# Current_Me.net
KiCad netlist of a schematic drawn in Altium Designer
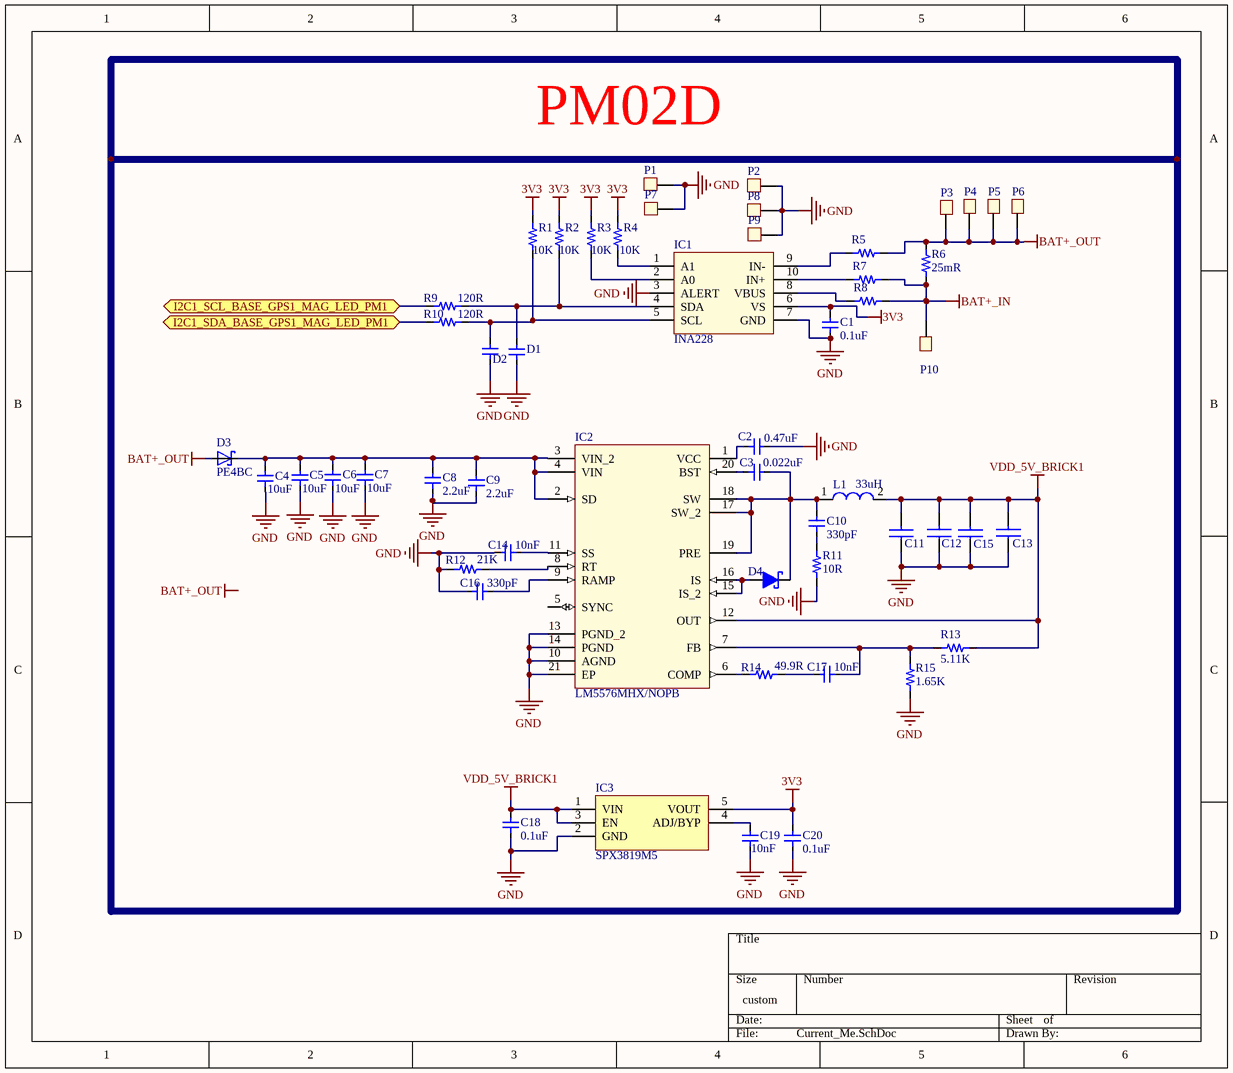
[diagram p0: Current_Me.SchDoc]

(export (version "E")
  (design (tool "Eeschema 10.0.6"))
  (components
    (comp (ref "C1")
      (value "0.1uF")
      (footprint "C0603")
      (description "CAP CER 0.1UF 25V X7R 0603")
      (libsource (lib "UAV_mainboard") (part "CC0603KRX7R8BB104"))
    )
    (comp (ref "C2")
      (value "0.47uF")
      (footprint "C0603")
      (description "0.47 µF ±10% 50V Ceramic Capacitor X5R 0603 (1608 Metric)")
      (libsource (lib "UAV_mainboard") (part "CC0603KRX5R9BB474"))
    )
    (comp (ref "C3")
      (value "0.022uF")
      (footprint "C0603")
      (description "0.022 µF ±10% 50V Ceramic Capacitor X7R 0603 (1608 Metric)")
      (libsource (lib "UAV_mainboard") (part "0603B223K500CT"))
    )
    (comp (ref "C4")
      (value "10uF")
      (footprint "C1206")
      (description "10 µF ±10% 100V Ceramic Capacitor X6S 1206 (3216 Metric)")
      (libsource (lib "UAV_mainboard") (part "C3216X6S2A106K160AC"))
    )
    (comp (ref "C5")
      (value "10uF")
      (footprint "C1206")
      (description "10 µF ±10% 100V Ceramic Capacitor X6S 1206 (3216 Metric)")
      (libsource (lib "UAV_mainboard") (part "C3216X6S2A106K160AC"))
    )
    (comp (ref "C6")
      (value "10uF")
      (footprint "C1206")
      (description "10 µF ±10% 100V Ceramic Capacitor X6S 1206 (3216 Metric)")
      (libsource (lib "UAV_mainboard") (part "C3216X6S2A106K160AC"))
    )
    (comp (ref "C7")
      (value "10uF")
      (footprint "C1206")
      (description "10 µF ±10% 100V Ceramic Capacitor X6S 1206 (3216 Metric)")
      (libsource (lib "UAV_mainboard") (part "C3216X6S2A106K160AC"))
    )
    (comp (ref "C8")
      (value "2.2uF")
      (footprint "C0603")
      (description "2.2 µF ±10% 10V Ceramic Capacitor X5R 0603 (1608 Metric)")
      (libsource (lib "UAV_mainboard") (part "CC0603KPX5R6BB225"))
    )
    (comp (ref "C9")
      (value "2.2uF")
      (footprint "C0603")
      (description "2.2 µF ±10% 10V Ceramic Capacitor X5R 0603 (1608 Metric)")
      (libsource (lib "UAV_mainboard") (part "CC0603KPX5R6BB225"))
    )
    (comp (ref "C10")
      (value "330pF")
      (footprint "C0603")
      (description "330 pF ±10% 25V Ceramic Capacitor X7R 0603 (1608 Metric)")
      (libsource (lib "UAV_mainboard") (part "CC0603KRX7R8BB331"))
    )
    (comp (ref "C11")
      (value "C2012X5R1A226M125AB")
      (footprint "C0805")
      (description "Multilayer Ceramic Capacitors MLCC - SMD/SMT 0805 10V 22uF X5R 20% T: 1.25mm")
      (libsource (lib "GPS_V3") (part "C2012X5R1A226M125AB"))
    )
    (comp (ref "C12")
      (value "C2012X5R1A226M125AB")
      (footprint "C0805")
      (description "Multilayer Ceramic Capacitors MLCC - SMD/SMT 0805 10V 22uF X5R 20% T: 1.25mm")
      (libsource (lib "GPS_V3") (part "C2012X5R1A226M125AB"))
    )
    (comp (ref "C13")
      (value "C2012X5R1A226M125AB")
      (footprint "C0805")
      (description "Multilayer Ceramic Capacitors MLCC - SMD/SMT 0805 10V 22uF X5R 20% T: 1.25mm")
      (libsource (lib "GPS_V3") (part "C2012X5R1A226M125AB"))
    )
    (comp (ref "C14")
      (value "10nF")
      (footprint "C0603")
      (description "10000 pF ±5% 25V Ceramic Capacitor X7R 0603 (1608 Metric)")
      (libsource (lib "UAV_mainboard") (part "CC0603JRX7R8BB103"))
    )
    (comp (ref "C15")
      (value "C2012X5R1A226M125AB")
      (footprint "C0805")
      (description "Multilayer Ceramic Capacitors MLCC - SMD/SMT 0805 10V 22uF X5R 20% T: 1.25mm")
      (libsource (lib "GPS_V3") (part "C2012X5R1A226M125AB"))
    )
    (comp (ref "C16")
      (value "330pF")
      (footprint "C0603")
      (description "330 pF ±10% 25V Ceramic Capacitor X7R 0603 (1608 Metric)")
      (libsource (lib "UAV_mainboard") (part "CC0603KRX7R8BB331"))
    )
    (comp (ref "C17")
      (value "10nF")
      (footprint "C0603")
      (description "10000 pF ±5% 25V Ceramic Capacitor X7R 0603 (1608 Metric)")
      (libsource (lib "UAV_mainboard") (part "CC0603JRX7R8BB103"))
    )
    (comp (ref "C18")
      (value "0.1uF")
      (footprint "C0603")
      (description "CAP CER 0.1UF 25V X7R 0603")
      (libsource (lib "UAV_mainboard") (part "CC0603KRX7R8BB104"))
    )
    (comp (ref "C19")
      (value "10nF")
      (footprint "C0603")
      (description "10000 pF ±5% 25V Ceramic Capacitor X7R 0603 (1608 Metric)")
      (libsource (lib "UAV_mainboard") (part "CC0603JRX7R8BB103"))
    )
    (comp (ref "C20")
      (value "0.1uF")
      (footprint "C0603")
      (description "CAP CER 0.1UF 25V X7R 0603")
      (libsource (lib "UAV_mainboard") (part "CC0603KRX7R8BB104"))
    )
    (comp (ref "D1")
      (value "PESD0402-140")
      (footprint "PESD0402-140")
      (description "40V Clamp - Ipp Tvs Diode Surface Mount 0402")
      (libsource (lib "UAV_mainboard") (part "PESD0402-140"))
    )
    (comp (ref "D2")
      (value "PESD0402-140")
      (footprint "PESD0402-140")
      (description "40V Clamp - Ipp Tvs Diode Surface Mount 0402")
      (libsource (lib "UAV_mainboard") (part "PESD0402-140"))
    )
    (comp (ref "D3")
      (value "PE4BC")
      (footprint "PE4BC")
      (description "Diode 100 V 4A Surface Mount DO-214AB (SMC)")
      (libsource (lib "UAV_mainboard") (part "PE4BC"))
    )
    (comp (ref "D4")
      (value "MBRS3100T3G")
      (footprint "MBRS3100T3G")
      (description "DIODE SCHOTTKY 100V 3A SMC")
      (libsource (lib "UAV_mainboard") (part "MBRS3100T3G"))
    )
    (comp (ref "IC1")
      (value "INA228")
      (footprint "VSSOP10")
      (description "Current & Power Monitors & Regulators AEC-Q100 85-V 20-b it ultraprecise I")
      (libsource (lib "UAV_mainboard") (part "INA228AQDGSRQ1"))
    )
    (comp (ref "IC2")
      (value "LM5576MHX/NOPB")
      (footprint "20HTSSOP")
      (description "IC REG BUCK ADJ 3A 20HTSSOP")
      (libsource (lib "UAV_mainboard") (part "LM5576MHX/NOPB"))
    )
    (comp (ref "IC3")
      (value "SPX3819M5")
      (footprint "SOT23-5")
      (description "IC REG LINEAR 3V 500MA SOT23-5")
      (libsource (lib "UAV_mainboard") (part "SPX3819M5-L-3-0/TR"))
    )
    (comp (ref "L1")
      (value "33uH")
      (footprint "MGAH1005330M-10")
      (description "Power Inductors - SMD 33uH 0.075ohm 5A")
      (libsource (lib "UAV_mainboard") (part "MGAH1005330M-10"))
    )
    (comp (ref "P1") (value "PAD_hàn 5x5") (footprint "PAD 5x5") (libsource (lib "") (part "PAD_hàn 5x5_2")))
    (comp (ref "P2") (value "PAD_hàn 5x5") (footprint "PAD 5x5") (libsource (lib "") (part "PAD_hàn 5x5_2")))
    (comp (ref "P3")
      (value "PAD_hàn 5x5")
      (footprint "PAD 5x5")
      (libsource (lib "UAV_mainboard") (part "PAD_hàn 5x5"))
    )
    (comp (ref "P4")
      (value "PAD_hàn 5x5")
      (footprint "PAD 5x5")
      (libsource (lib "UAV_mainboard") (part "PAD_hàn 5x5"))
    )
    (comp (ref "P5")
      (value "PAD_hàn 5x5")
      (footprint "PAD 5x5")
      (libsource (lib "UAV_mainboard") (part "PAD_hàn 5x5"))
    )
    (comp (ref "P6")
      (value "PAD_hàn 5x5")
      (footprint "PAD 5x5")
      (libsource (lib "UAV_mainboard") (part "PAD_hàn 5x5"))
    )
    (comp (ref "P7") (value "PAD_hàn 5x5") (footprint "PAD 5x5") (libsource (lib "") (part "PAD_hàn 5x5_2")))
    (comp (ref "P8") (value "PAD_hàn 5x5") (footprint "PAD 5x5") (libsource (lib "") (part "PAD_hàn 5x5_2")))
    (comp (ref "P9") (value "PAD_hàn 5x5") (footprint "PAD 5x5") (libsource (lib "") (part "PAD_hàn 5x5_2")))
    (comp (ref "P10") (value "PAD_hàn 5x5") (footprint "PAD 5x5") (libsource (lib "") (part "PAD_hàn 5x5_1")))
    (comp (ref "R1")
      (value "10K")
      (footprint "R0402")
      (description "RES SMD 10K OHM 1% 1/16W 0402")
      (libsource (lib "UAV_mainboard") (part "RC1005F103CS"))
    )
    (comp (ref "R2")
      (value "10K")
      (footprint "R0402")
      (description "RES SMD 10K OHM 1% 1/16W 0402")
      (libsource (lib "UAV_mainboard") (part "RC1005F103CS"))
    )
    (comp (ref "R3")
      (value "10K")
      (footprint "R0402")
      (description "RES SMD 10K OHM 1% 1/16W 0402")
      (libsource (lib "UAV_mainboard") (part "RC1005F103CS"))
    )
    (comp (ref "R4")
      (value "10K")
      (footprint "R0402")
      (description "RES SMD 10K OHM 1% 1/16W 0402")
      (libsource (lib "UAV_mainboard") (part "RC1005F103CS"))
    )
    (comp (ref "R5")
      (value "0R/0402")
      (footprint "R0402")
      (libsource (lib "UAV_mainboard") (part "CR0402AJ/-000GAS"))
    )
    (comp (ref "R6")
      (value "25mR")
      (footprint "R2818")
      (libsource (lib "UAV_mainboard") (part "WSHP2818R0250FEA"))
    )
    (comp (ref "R7")
      (value "0R/0402")
      (footprint "R0402")
      (libsource (lib "UAV_mainboard") (part "CR0402AJ/-000GAS"))
    )
    (comp (ref "R8")
      (value "0R/0402")
      (footprint "R0402")
      (libsource (lib "UAV_mainboard") (part "CR0402AJ/-000GAS"))
    )
    (comp (ref "R9")
      (value "120R")
      (footprint "R0402")
      (description "120 Ohms ±1% 0.063W, 1/16W Chip Resistor 0402 (1005 Metric) Moisture Resistant Thick Film")
      (libsource (lib "UAV_mainboard") (part "RC0402FR-07120RL"))
    )
    (comp (ref "R10")
      (value "120R")
      (footprint "R0402")
      (description "120 Ohms ±1% 0.063W, 1/16W Chip Resistor 0402 (1005 Metric) Moisture Resistant Thick Film")
      (libsource (lib "UAV_mainboard") (part "RC0402FR-07120RL"))
    )
    (comp (ref "R11")
      (value "10R")
      (footprint "R0603")
      (description "10 Ohms ±1% 0.1W, 1/10W Chip Resistor 0603 (1608 Metric) Automotive AEC-Q200 Thick Film")
      (libsource (lib "UAV_mainboard") (part "RMCF0603FT10R0"))
    )
    (comp (ref "R12")
      (value "21K")
      (footprint "R0402")
      (description "21 kOhms ±1% 0.063W, 1/16W Chip Resistor 0402 (1005 Metric) Moisture Resistant Thick Film")
      (libsource (lib "UAV_mainboard") (part "RC0402FR-0721KL"))
    )
    (comp (ref "R13")
      (value "5.11K")
      (footprint "R0402")
      (description "5.11 kOhms ±1% 0.1W, 1/10W Chip Resistor 0402 (1005 Metric) Automotive AEC-Q200 Thick Film")
      (libsource (lib "UAV_mainboard") (part "ERJ-2RKF5111X"))
    )
    (comp (ref "R14")
      (value "49.9R")
      (footprint "R0402")
      (libsource (lib "UAV_mainboard") (part "CRT0402ABY-49R9GLF"))
    )
    (comp (ref "R15")
      (value "1.65K")
      (footprint "R0402")
      (description "RES 1.65K OHM 1% 1/16W 0402")
      (libsource (lib "UAV_mainboard") (part "RC0402FR-071K65L"))
    )
  )
  (nets
    (net (code "1") (name "/I2C1_SCL_BASE_GPS1_MAG_LED_PM1") (class "Default")
      (node (ref "R9") (pin "1") (pinfunction "1_1") (pintype "passive"))
    )
    (net (code "2") (name "/I2C1_SDA_BASE_GPS1_MAG_LED_PM1") (class "Default")
      (node (ref "R10") (pin "1") (pinfunction "1_1") (pintype "passive"))
    )
    (net (code "3") (name "3V3") (class "Default")
      (node (ref "C1") (pin "2") (pinfunction "2_2") (pintype "passive"))
      (node (ref "C20") (pin "2") (pinfunction "2_2") (pintype "passive"))
      (node (ref "IC1") (pin "6") (pinfunction "VS_6") (pintype "passive"))
      (node (ref "IC3") (pin "5") (pinfunction "VOUT_5") (pintype "passive"))
      (node (ref "R1") (pin "2") (pinfunction "2_2") (pintype "passive"))
      (node (ref "R2") (pin "2") (pinfunction "2_2") (pintype "passive"))
      (node (ref "R3") (pin "2") (pinfunction "2_2") (pintype "passive"))
      (node (ref "R4") (pin "2") (pinfunction "2_2") (pintype "passive"))
    )
    (net (code "4") (name "BAT+_IN") (class "Default")
      (node (ref "P10") (pin "1") (pinfunction "1_1") (pintype "passive"))
      (node (ref "R6") (pin "1") (pinfunction "1_1") (pintype "passive"))
      (node (ref "R7") (pin "2") (pinfunction "2_2") (pintype "passive"))
      (node (ref "R8") (pin "2") (pinfunction "2_2") (pintype "passive"))
    )
    (net (code "5") (name "BAT+_OUT") (class "Default")
      (node (ref "D3") (pin "2") (pinfunction "A_2") (pintype "passive"))
      (node (ref "P3") (pin "1") (pinfunction "1_1") (pintype "passive"))
      (node (ref "P4") (pin "1") (pinfunction "1_1") (pintype "passive"))
      (node (ref "P5") (pin "1") (pinfunction "1_1") (pintype "passive"))
      (node (ref "P6") (pin "1") (pinfunction "1_1") (pintype "passive"))
      (node (ref "R5") (pin "2") (pinfunction "2_2") (pintype "passive"))
      (node (ref "R6") (pin "2") (pinfunction "2_2") (pintype "passive"))
    )
    (net (code "6") (name "GND") (class "Default")
      (node (ref "C1") (pin "1") (pinfunction "1_1") (pintype "passive"))
      (node (ref "C11") (pin "1") (pinfunction "1_1") (pintype "passive"))
      (node (ref "C12") (pin "1") (pinfunction "1_1") (pintype "passive"))
      (node (ref "C13") (pin "1") (pinfunction "1_1") (pintype "passive"))
      (node (ref "C14") (pin "2") (pinfunction "2_2") (pintype "passive"))
      (node (ref "C15") (pin "1") (pinfunction "1_1") (pintype "passive"))
      (node (ref "C16") (pin "1") (pinfunction "1_1") (pintype "passive"))
      (node (ref "C18") (pin "1") (pinfunction "1_1") (pintype "passive"))
      (node (ref "C19") (pin "1") (pinfunction "1_1") (pintype "passive"))
      (node (ref "C2") (pin "2") (pinfunction "2_2") (pintype "passive"))
      (node (ref "C20") (pin "1") (pinfunction "1_1") (pintype "passive"))
      (node (ref "C4") (pin "1") (pinfunction "1_1") (pintype "passive"))
      (node (ref "C5") (pin "1") (pinfunction "1_1") (pintype "passive"))
      (node (ref "C6") (pin "1") (pinfunction "1_1") (pintype "passive"))
      (node (ref "C7") (pin "1") (pinfunction "1_1") (pintype "passive"))
      (node (ref "C8") (pin "1") (pinfunction "1_1") (pintype "passive"))
      (node (ref "C9") (pin "1") (pinfunction "1_1") (pintype "passive"))
      (node (ref "D1") (pin "1") (pinfunction "1_1") (pintype "passive"))
      (node (ref "D2") (pin "1") (pinfunction "1_1") (pintype "passive"))
      (node (ref "IC1") (pin "3") (pinfunction "ALERT_3") (pintype "passive"))
      (node (ref "IC1") (pin "7") (pinfunction "GND_7") (pintype "passive"))
      (node (ref "IC2") (pin "10") (pinfunction "AGND_10") (pintype "passive"))
      (node (ref "IC2") (pin "13") (pinfunction "PGND_2_13") (pintype "passive"))
      (node (ref "IC2") (pin "14") (pinfunction "PGND_14") (pintype "passive"))
      (node (ref "IC2") (pin "21") (pinfunction "EP_21") (pintype "passive"))
      (node (ref "IC3") (pin "2") (pinfunction "GND_2") (pintype "passive"))
      (node (ref "P1") (pin "1") (pinfunction "1_1") (pintype "passive"))
      (node (ref "P2") (pin "1") (pinfunction "1_1") (pintype "passive"))
      (node (ref "P7") (pin "1") (pinfunction "1_1") (pintype "passive"))
      (node (ref "P8") (pin "1") (pinfunction "1_1") (pintype "passive"))
      (node (ref "P9") (pin "1") (pinfunction "1_1") (pintype "passive"))
      (node (ref "R11") (pin "1") (pinfunction "1_1") (pintype "passive"))
      (node (ref "R12") (pin "1") (pinfunction "1_1") (pintype "passive"))
      (node (ref "R15") (pin "1") (pinfunction "1_1") (pintype "passive"))
    )
    (net (code "7") (name "Net-(C10-Pad1)") (class "Default")
      (node (ref "C10") (pin "1") (pinfunction "1_1") (pintype "passive"))
      (node (ref "R11") (pin "2") (pinfunction "2_2") (pintype "passive"))
    )
    (net (code "8") (name "Net-(C17-Pad2)") (class "Default")
      (node (ref "C17") (pin "2") (pinfunction "2_2") (pintype "passive"))
      (node (ref "R14") (pin "2") (pinfunction "2_2") (pintype "passive"))
    )
    (net (code "9") (name "Net-(D3-C)") (class "Default")
      (node (ref "C4") (pin "2") (pinfunction "2_2") (pintype "passive"))
      (node (ref "C5") (pin "2") (pinfunction "2_2") (pintype "passive"))
      (node (ref "C6") (pin "2") (pinfunction "2_2") (pintype "passive"))
      (node (ref "C7") (pin "2") (pinfunction "2_2") (pintype "passive"))
      (node (ref "C8") (pin "2") (pinfunction "2_2") (pintype "passive"))
      (node (ref "C9") (pin "2") (pinfunction "2_2") (pintype "passive"))
      (node (ref "D3") (pin "1") (pinfunction "C_1") (pintype "passive"))
      (node (ref "IC2") (pin "2") (pinfunction "SD_2") (pintype "input"))
      (node (ref "IC2") (pin "3") (pinfunction "VIN_2_3") (pintype "power_in"))
      (node (ref "IC2") (pin "4") (pinfunction "VIN_4") (pintype "power_in"))
    )
    (net (code "10") (name "Net-(D4-A)") (class "Default")
      (node (ref "D4") (pin "1") (pinfunction "A_1") (pintype "passive"))
      (node (ref "IC2") (pin "15") (pinfunction "IS_2_15") (pintype "input"))
      (node (ref "IC2") (pin "16") (pinfunction "IS_16") (pintype "input"))
    )
    (net (code "11") (name "Net-(D4-K)") (class "Default")
      (node (ref "C10") (pin "2") (pinfunction "2_2") (pintype "passive"))
      (node (ref "C3") (pin "2") (pinfunction "2_2") (pintype "passive"))
      (node (ref "D4") (pin "2") (pinfunction "K_2") (pintype "passive"))
      (node (ref "IC2") (pin "17") (pinfunction "SW_2_17") (pintype "passive"))
      (node (ref "IC2") (pin "18") (pinfunction "SW_18") (pintype "passive"))
      (node (ref "IC2") (pin "19") (pinfunction "PRE_19") (pintype "passive"))
      (node (ref "L1") (pin "1") (pinfunction "1_1") (pintype "passive"))
    )
    (net (code "12") (name "Net-(IC1-A0)") (class "Default")
      (node (ref "IC1") (pin "2") (pinfunction "A0_2") (pintype "passive"))
      (node (ref "R3") (pin "1") (pinfunction "1_1") (pintype "passive"))
    )
    (net (code "13") (name "Net-(IC1-A1)") (class "Default")
      (node (ref "IC1") (pin "1") (pinfunction "A1_1") (pintype "passive"))
      (node (ref "R4") (pin "1") (pinfunction "1_1") (pintype "passive"))
    )
    (net (code "14") (name "Net-(IC1-IN+)") (class "Default")
      (node (ref "IC1") (pin "10") (pinfunction "IN+_10") (pintype "passive"))
      (node (ref "R7") (pin "1") (pinfunction "1_1") (pintype "passive"))
    )
    (net (code "15") (name "Net-(IC1-IN-)") (class "Default")
      (node (ref "IC1") (pin "9") (pinfunction "IN-_9") (pintype "passive"))
      (node (ref "R5") (pin "1") (pinfunction "1_1") (pintype "passive"))
    )
    (net (code "16") (name "Net-(IC1-SCL)") (class "Default")
      (node (ref "D2") (pin "2") (pinfunction "2_2") (pintype "passive"))
      (node (ref "IC1") (pin "5") (pinfunction "SCL_5") (pintype "passive"))
      (node (ref "R1") (pin "1") (pinfunction "1_1") (pintype "passive"))
      (node (ref "R10") (pin "2") (pinfunction "2_2") (pintype "passive"))
    )
    (net (code "17") (name "Net-(IC1-SDA)") (class "Default")
      (node (ref "D1") (pin "2") (pinfunction "2_2") (pintype "passive"))
      (node (ref "IC1") (pin "4") (pinfunction "SDA_4") (pintype "passive"))
      (node (ref "R2") (pin "1") (pinfunction "1_1") (pintype "passive"))
      (node (ref "R9") (pin "2") (pinfunction "2_2") (pintype "passive"))
    )
    (net (code "18") (name "Net-(IC1-VBUS)") (class "Default")
      (node (ref "IC1") (pin "8") (pinfunction "VBUS_8") (pintype "passive"))
      (node (ref "R8") (pin "1") (pinfunction "1_1") (pintype "passive"))
    )
    (net (code "19") (name "Net-(IC2-BST)") (class "Default")
      (node (ref "C3") (pin "1") (pinfunction "1_1") (pintype "passive"))
      (node (ref "IC2") (pin "20") (pinfunction "BST_20") (pintype "input"))
    )
    (net (code "20") (name "Net-(IC2-COMP)") (class "Default")
      (node (ref "IC2") (pin "6") (pinfunction "COMP_6") (pintype "output"))
      (node (ref "R14") (pin "1") (pinfunction "1_1") (pintype "passive"))
    )
    (net (code "21") (name "Net-(IC2-FB)") (class "Default")
      (node (ref "C17") (pin "1") (pinfunction "1_1") (pintype "passive"))
      (node (ref "IC2") (pin "7") (pinfunction "FB_7") (pintype "output"))
      (node (ref "R13") (pin "1") (pinfunction "1_1") (pintype "passive"))
      (node (ref "R15") (pin "2") (pinfunction "2_2") (pintype "passive"))
    )
    (net (code "22") (name "Net-(IC2-RAMP)") (class "Default")
      (node (ref "C16") (pin "2") (pinfunction "2_2") (pintype "passive"))
      (node (ref "IC2") (pin "9") (pinfunction "RAMP_9") (pintype "input"))
    )
    (net (code "23") (name "Net-(IC2-RT)") (class "Default")
      (node (ref "IC2") (pin "8") (pinfunction "RT_8") (pintype "input"))
      (node (ref "R12") (pin "2") (pinfunction "2_2") (pintype "passive"))
    )
    (net (code "24") (name "Net-(IC2-SS)") (class "Default")
      (node (ref "C14") (pin "1") (pinfunction "1_1") (pintype "passive"))
      (node (ref "IC2") (pin "11") (pinfunction "SS_11") (pintype "input"))
    )
    (net (code "25") (name "Net-(IC2-VCC)") (class "Default")
      (node (ref "C2") (pin "1") (pinfunction "1_1") (pintype "passive"))
      (node (ref "IC2") (pin "1") (pinfunction "VCC_1") (pintype "power_in"))
    )
    (net (code "26") (name "Net-(IC3-ADJ{slash}BYP)") (class "Default")
      (node (ref "C19") (pin "2") (pinfunction "2_2") (pintype "passive"))
      (node (ref "IC3") (pin "4") (pinfunction "ADJ/BYP_4") (pintype "passive"))
    )
    (net (code "27") (name "VDD_5V_BRICK1") (class "Default")
      (node (ref "C11") (pin "2") (pinfunction "2_2") (pintype "passive"))
      (node (ref "C12") (pin "2") (pinfunction "2_2") (pintype "passive"))
      (node (ref "C13") (pin "2") (pinfunction "2_2") (pintype "passive"))
      (node (ref "C15") (pin "2") (pinfunction "2_2") (pintype "passive"))
      (node (ref "C18") (pin "2") (pinfunction "2_2") (pintype "passive"))
      (node (ref "IC2") (pin "12") (pinfunction "OUT_12") (pintype "output"))
      (node (ref "IC3") (pin "1") (pinfunction "VIN_1") (pintype "passive"))
      (node (ref "IC3") (pin "3") (pinfunction "EN_3") (pintype "passive"))
      (node (ref "L1") (pin "2") (pinfunction "2_2") (pintype "passive"))
      (node (ref "R13") (pin "2") (pinfunction "2_2") (pintype "passive"))
    )
    (net (code "28") (name "unconnected-(IC2-SYNC-Pad5)") (class "Default")
      (node (ref "IC2") (pin "5") (pinfunction "SYNC_5") (pintype "bidirectional"))
    )
  )
)
